# connector_board_final_schematic.net
KiCad netlist of a schematic drawn in EAGLE
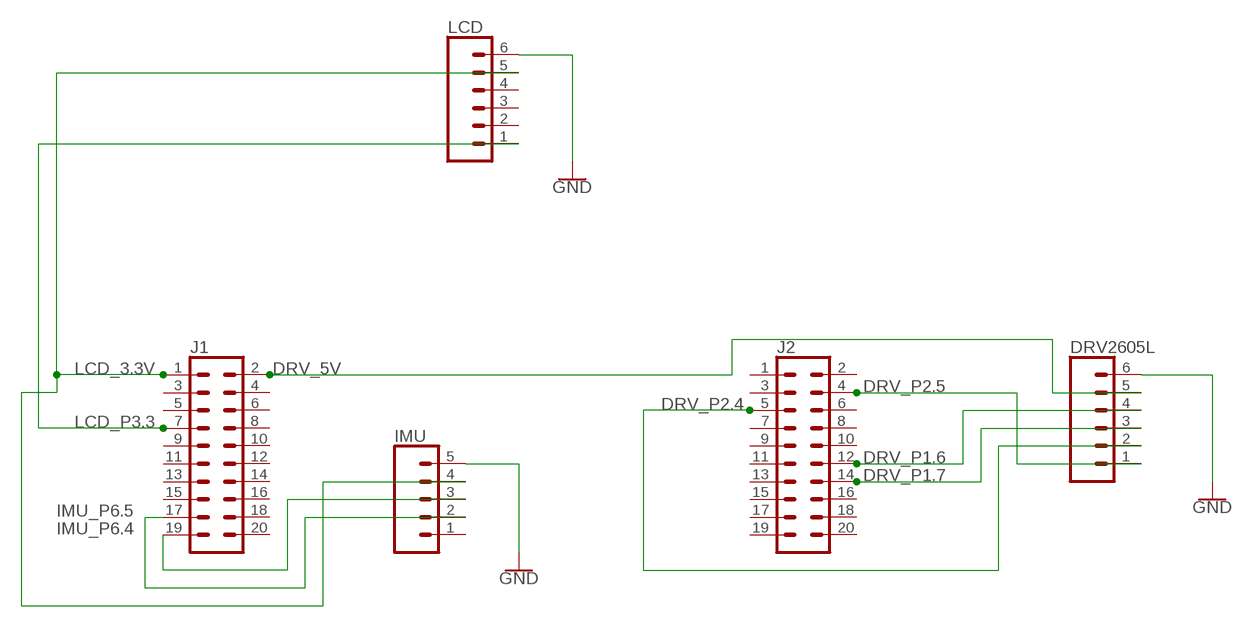
[diagram p0: schematic, sheet 1]

(export (version "E")
  (design (tool "Eeschema 10.0.6"))
  (components
    (comp (ref "DRV2605L")
      (value "CONN_06SILK_FEMALE_PTH")
      (footprint "eagle-import:1X06")
      (libsource (lib "eagle-import") (part "CONN_06SILK_FEMALE_PTH"))
    )
    (comp (ref "IMU")
      (value "CONN_05")
      (footprint "eagle-import:1X05")
      (libsource (lib "eagle-import") (part "CONN_05"))
    )
    (comp (ref "J1")
      (value "CONN_10X2")
      (footprint "eagle-import:2X10")
      (libsource (lib "eagle-import") (part "CONN_10X2"))
    )
    (comp (ref "J2")
      (value "CONN_10X2")
      (footprint "eagle-import:2X10")
      (libsource (lib "eagle-import") (part "CONN_10X2"))
    )
    (comp (ref "LCD")
      (value "CONN_06SILK_FEMALE_PTH")
      (footprint "eagle-import:1X06")
      (libsource (lib "eagle-import") (part "CONN_06SILK_FEMALE_PTH"))
    )
  )
  (nets
    (net (code "1") (name "/DRV_5V") (class "Default")
      (node (ref "DRV2605L") (pin "5") (pinfunction "5_5") (pintype "passive"))
      (node (ref "J1") (pin "2") (pinfunction "2_2") (pintype "passive"))
    )
    (net (code "2") (name "/DRV_P1.6") (class "Default")
      (node (ref "DRV2605L") (pin "4") (pinfunction "4_4") (pintype "passive"))
      (node (ref "J2") (pin "12") (pinfunction "12_12") (pintype "passive"))
    )
    (net (code "3") (name "/DRV_P1.7") (class "Default")
      (node (ref "DRV2605L") (pin "3") (pinfunction "3_3") (pintype "passive"))
      (node (ref "J2") (pin "14") (pinfunction "14_14") (pintype "passive"))
    )
    (net (code "4") (name "/DRV_P2.4") (class "Default")
      (node (ref "DRV2605L") (pin "2") (pinfunction "2_2") (pintype "passive"))
      (node (ref "J2") (pin "5") (pinfunction "5_5") (pintype "passive"))
    )
    (net (code "5") (name "/DRV_P2.5") (class "Default")
      (node (ref "DRV2605L") (pin "1") (pinfunction "1_1") (pintype "passive"))
      (node (ref "J2") (pin "4") (pinfunction "4_4") (pintype "passive"))
    )
    (net (code "6") (name "/IMU_P6.4") (class "Default")
      (node (ref "IMU") (pin "3") (pinfunction "3_3") (pintype "passive"))
      (node (ref "J1") (pin "19") (pinfunction "19_19") (pintype "passive"))
    )
    (net (code "7") (name "/IMU_P6.5") (class "Default")
      (node (ref "IMU") (pin "2") (pinfunction "2_2") (pintype "passive"))
      (node (ref "J1") (pin "17") (pinfunction "17_17") (pintype "passive"))
    )
    (net (code "8") (name "/LCD_3.3V") (class "Default")
      (node (ref "IMU") (pin "4") (pinfunction "4_4") (pintype "passive"))
      (node (ref "J1") (pin "1") (pinfunction "1_1") (pintype "passive"))
      (node (ref "LCD") (pin "5") (pinfunction "5_5") (pintype "passive"))
    )
    (net (code "9") (name "/LCD_P3.3") (class "Default")
      (node (ref "J1") (pin "7") (pinfunction "7_7") (pintype "passive"))
      (node (ref "LCD") (pin "1") (pinfunction "1_1") (pintype "passive"))
    )
    (net (code "10") (name "GND") (class "Default")
      (node (ref "DRV2605L") (pin "6") (pinfunction "6_6") (pintype "passive"))
      (node (ref "IMU") (pin "5") (pinfunction "5_5") (pintype "passive"))
      (node (ref "LCD") (pin "6") (pinfunction "6_6") (pintype "passive"))
    )
    (net (code "11") (name "unconnected-(IMU-Pad1)") (class "Default")
      (node (ref "IMU") (pin "1") (pinfunction "1_1") (pintype "passive"))
    )
    (net (code "12") (name "unconnected-(J1-Pad3)") (class "Default")
      (node (ref "J1") (pin "3") (pinfunction "3_3") (pintype "passive"))
    )
    (net (code "13") (name "unconnected-(J1-Pad4)") (class "Default")
      (node (ref "J1") (pin "4") (pinfunction "4_4") (pintype "passive"))
    )
    (net (code "14") (name "unconnected-(J1-Pad5)") (class "Default")
      (node (ref "J1") (pin "5") (pinfunction "5_5") (pintype "passive"))
    )
    (net (code "15") (name "unconnected-(J1-Pad6)") (class "Default")
      (node (ref "J1") (pin "6") (pinfunction "6_6") (pintype "passive"))
    )
    (net (code "16") (name "unconnected-(J1-Pad8)") (class "Default")
      (node (ref "J1") (pin "8") (pinfunction "8_8") (pintype "passive"))
    )
    (net (code "17") (name "unconnected-(J1-Pad9)") (class "Default")
      (node (ref "J1") (pin "9") (pinfunction "9_9") (pintype "passive"))
    )
    (net (code "18") (name "unconnected-(J1-Pad10)") (class "Default")
      (node (ref "J1") (pin "10") (pinfunction "10_10") (pintype "passive"))
    )
    (net (code "19") (name "unconnected-(J1-Pad11)") (class "Default")
      (node (ref "J1") (pin "11") (pinfunction "11_11") (pintype "passive"))
    )
    (net (code "20") (name "unconnected-(J1-Pad12)") (class "Default")
      (node (ref "J1") (pin "12") (pinfunction "12_12") (pintype "passive"))
    )
    (net (code "21") (name "unconnected-(J1-Pad13)") (class "Default")
      (node (ref "J1") (pin "13") (pinfunction "13_13") (pintype "passive"))
    )
    (net (code "22") (name "unconnected-(J1-Pad14)") (class "Default")
      (node (ref "J1") (pin "14") (pinfunction "14_14") (pintype "passive"))
    )
    (net (code "23") (name "unconnected-(J1-Pad15)") (class "Default")
      (node (ref "J1") (pin "15") (pinfunction "15_15") (pintype "passive"))
    )
    (net (code "24") (name "unconnected-(J1-Pad16)") (class "Default")
      (node (ref "J1") (pin "16") (pinfunction "16_16") (pintype "passive"))
    )
    (net (code "25") (name "unconnected-(J1-Pad18)") (class "Default")
      (node (ref "J1") (pin "18") (pinfunction "18_18") (pintype "passive"))
    )
    (net (code "26") (name "unconnected-(J1-Pad20)") (class "Default")
      (node (ref "J1") (pin "20") (pinfunction "20_20") (pintype "passive"))
    )
    (net (code "27") (name "unconnected-(J2-Pad1)") (class "Default")
      (node (ref "J2") (pin "1") (pinfunction "1_1") (pintype "passive"))
    )
    (net (code "28") (name "unconnected-(J2-Pad2)") (class "Default")
      (node (ref "J2") (pin "2") (pinfunction "2_2") (pintype "passive"))
    )
    (net (code "29") (name "unconnected-(J2-Pad3)") (class "Default")
      (node (ref "J2") (pin "3") (pinfunction "3_3") (pintype "passive"))
    )
    (net (code "30") (name "unconnected-(J2-Pad6)") (class "Default")
      (node (ref "J2") (pin "6") (pinfunction "6_6") (pintype "passive"))
    )
    (net (code "31") (name "unconnected-(J2-Pad7)") (class "Default")
      (node (ref "J2") (pin "7") (pinfunction "7_7") (pintype "passive"))
    )
    (net (code "32") (name "unconnected-(J2-Pad8)") (class "Default")
      (node (ref "J2") (pin "8") (pinfunction "8_8") (pintype "passive"))
    )
    (net (code "33") (name "unconnected-(J2-Pad9)") (class "Default")
      (node (ref "J2") (pin "9") (pinfunction "9_9") (pintype "passive"))
    )
    (net (code "34") (name "unconnected-(J2-Pad10)") (class "Default")
      (node (ref "J2") (pin "10") (pinfunction "10_10") (pintype "passive"))
    )
    (net (code "35") (name "unconnected-(J2-Pad11)") (class "Default")
      (node (ref "J2") (pin "11") (pinfunction "11_11") (pintype "passive"))
    )
    (net (code "36") (name "unconnected-(J2-Pad13)") (class "Default")
      (node (ref "J2") (pin "13") (pinfunction "13_13") (pintype "passive"))
    )
    (net (code "37") (name "unconnected-(J2-Pad15)") (class "Default")
      (node (ref "J2") (pin "15") (pinfunction "15_15") (pintype "passive"))
    )
    (net (code "38") (name "unconnected-(J2-Pad16)") (class "Default")
      (node (ref "J2") (pin "16") (pinfunction "16_16") (pintype "passive"))
    )
    (net (code "39") (name "unconnected-(J2-Pad17)") (class "Default")
      (node (ref "J2") (pin "17") (pinfunction "17_17") (pintype "passive"))
    )
    (net (code "40") (name "unconnected-(J2-Pad18)") (class "Default")
      (node (ref "J2") (pin "18") (pinfunction "18_18") (pintype "passive"))
    )
    (net (code "41") (name "unconnected-(J2-Pad19)") (class "Default")
      (node (ref "J2") (pin "19") (pinfunction "19_19") (pintype "passive"))
    )
    (net (code "42") (name "unconnected-(J2-Pad20)") (class "Default")
      (node (ref "J2") (pin "20") (pinfunction "20_20") (pintype "passive"))
    )
    (net (code "43") (name "unconnected-(LCD-Pad2)") (class "Default")
      (node (ref "LCD") (pin "2") (pinfunction "2_2") (pintype "passive"))
    )
    (net (code "44") (name "unconnected-(LCD-Pad3)") (class "Default")
      (node (ref "LCD") (pin "3") (pinfunction "3_3") (pintype "passive"))
    )
    (net (code "45") (name "unconnected-(LCD-Pad4)") (class "Default")
      (node (ref "LCD") (pin "4") (pinfunction "4_4") (pintype "passive"))
    )
  )
)
